# Mtx12BR.net
KiCad netlist of a schematic drawn in EAGLE
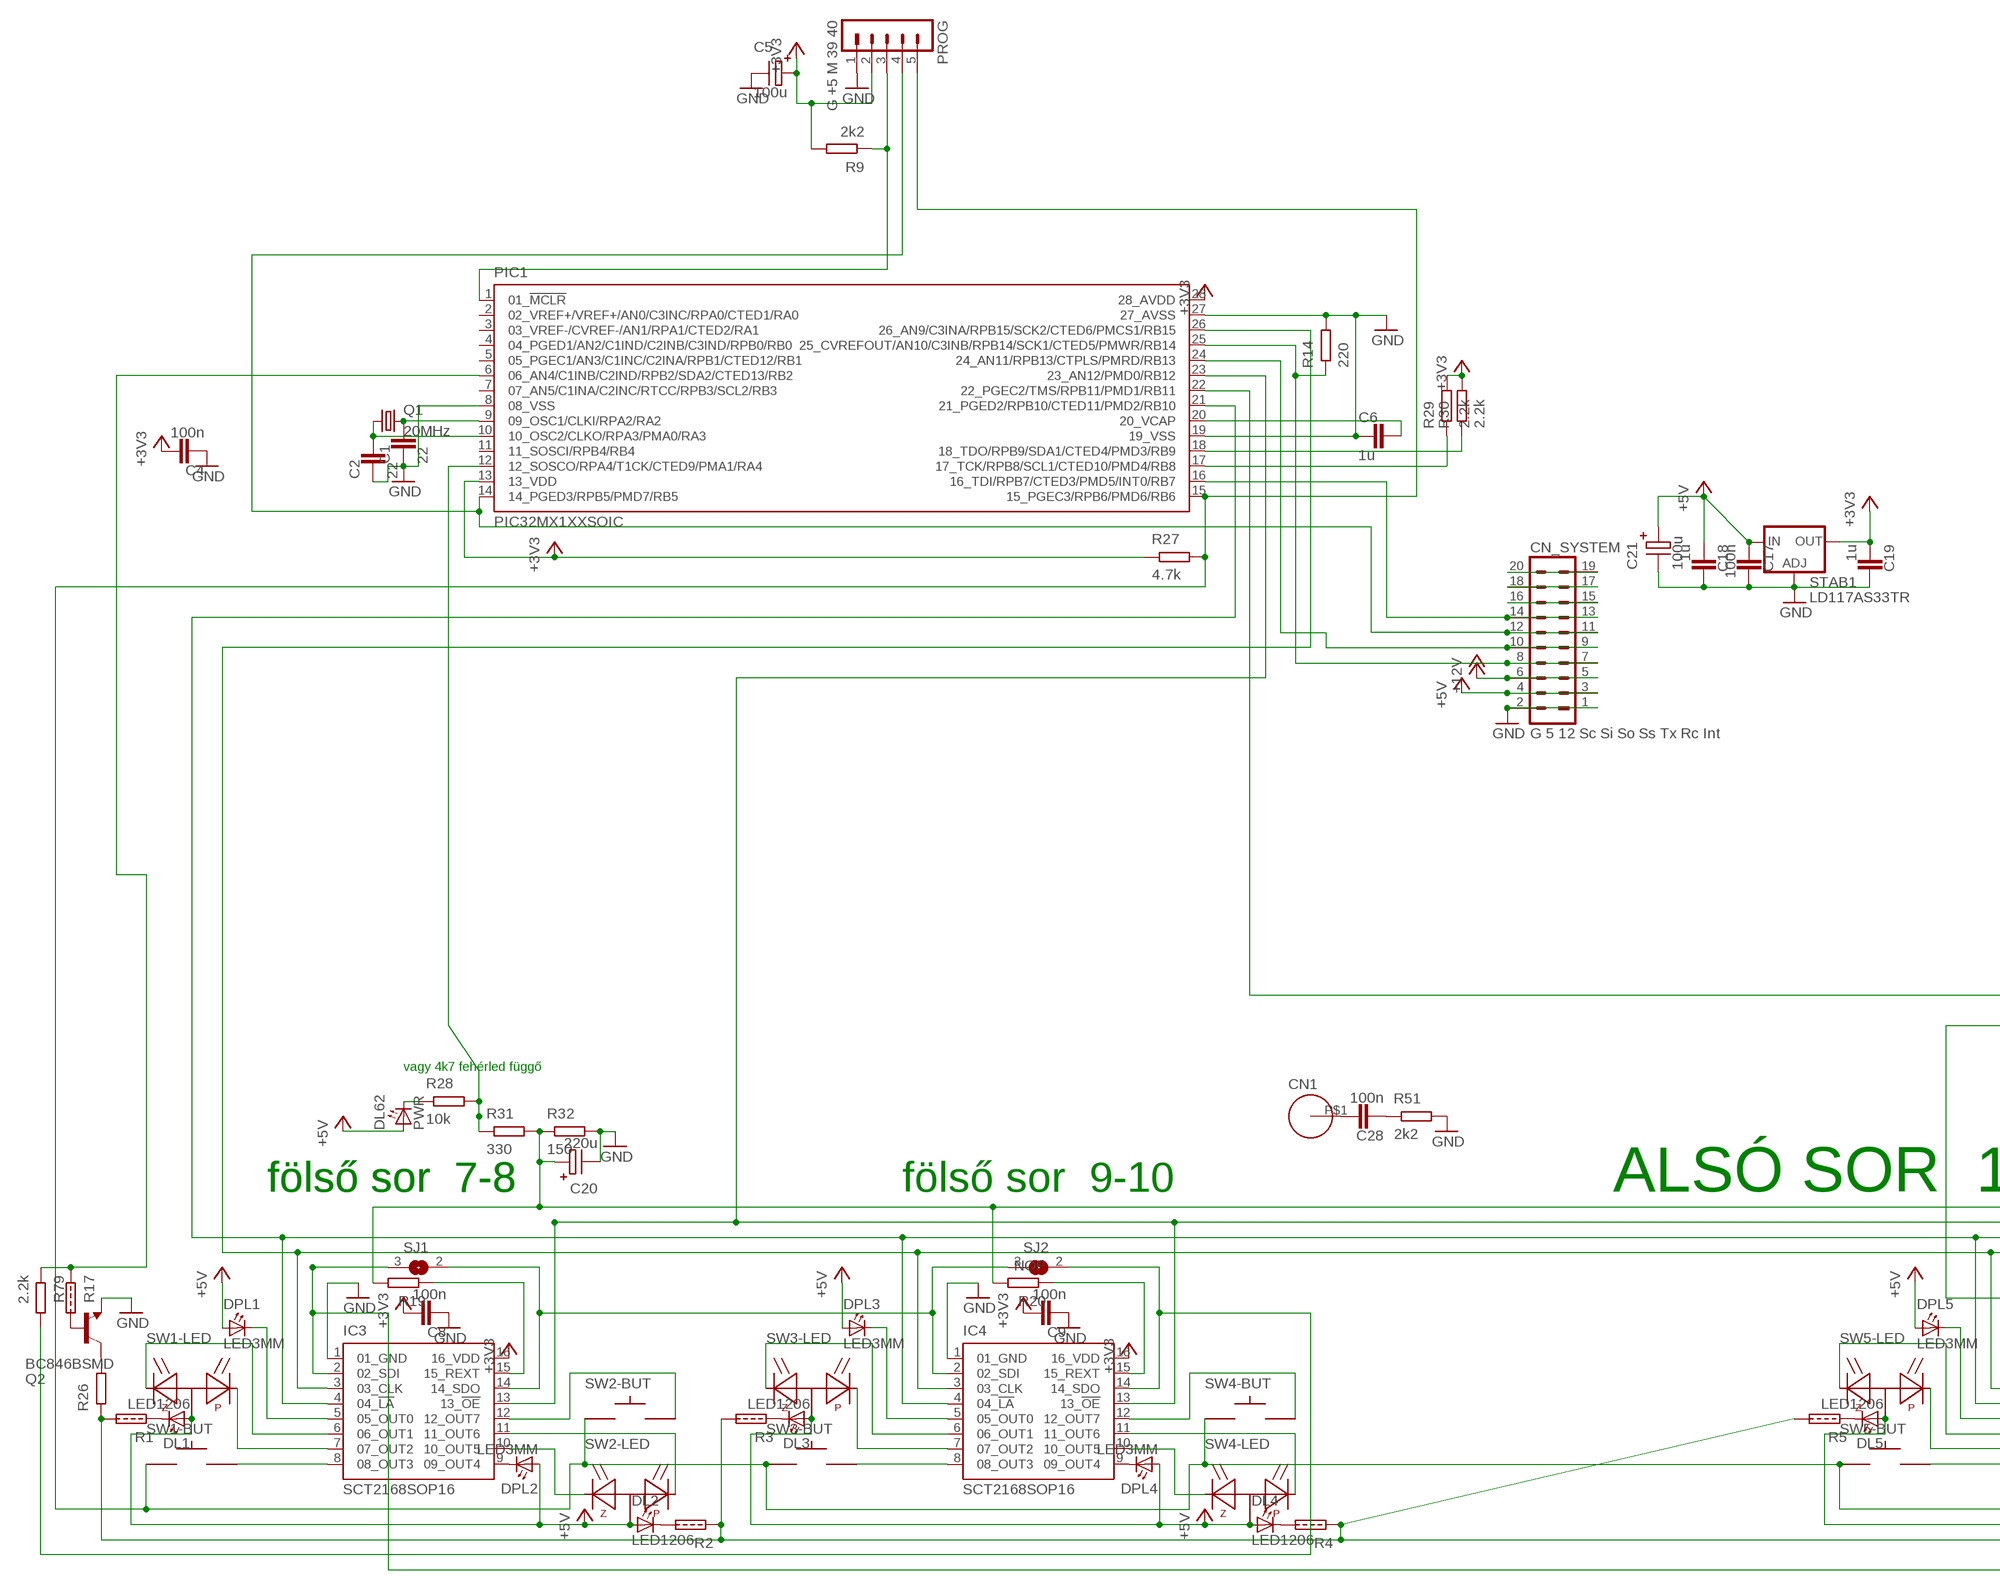
[diagram p0: schematic, sheet 1, part 1 of 2]
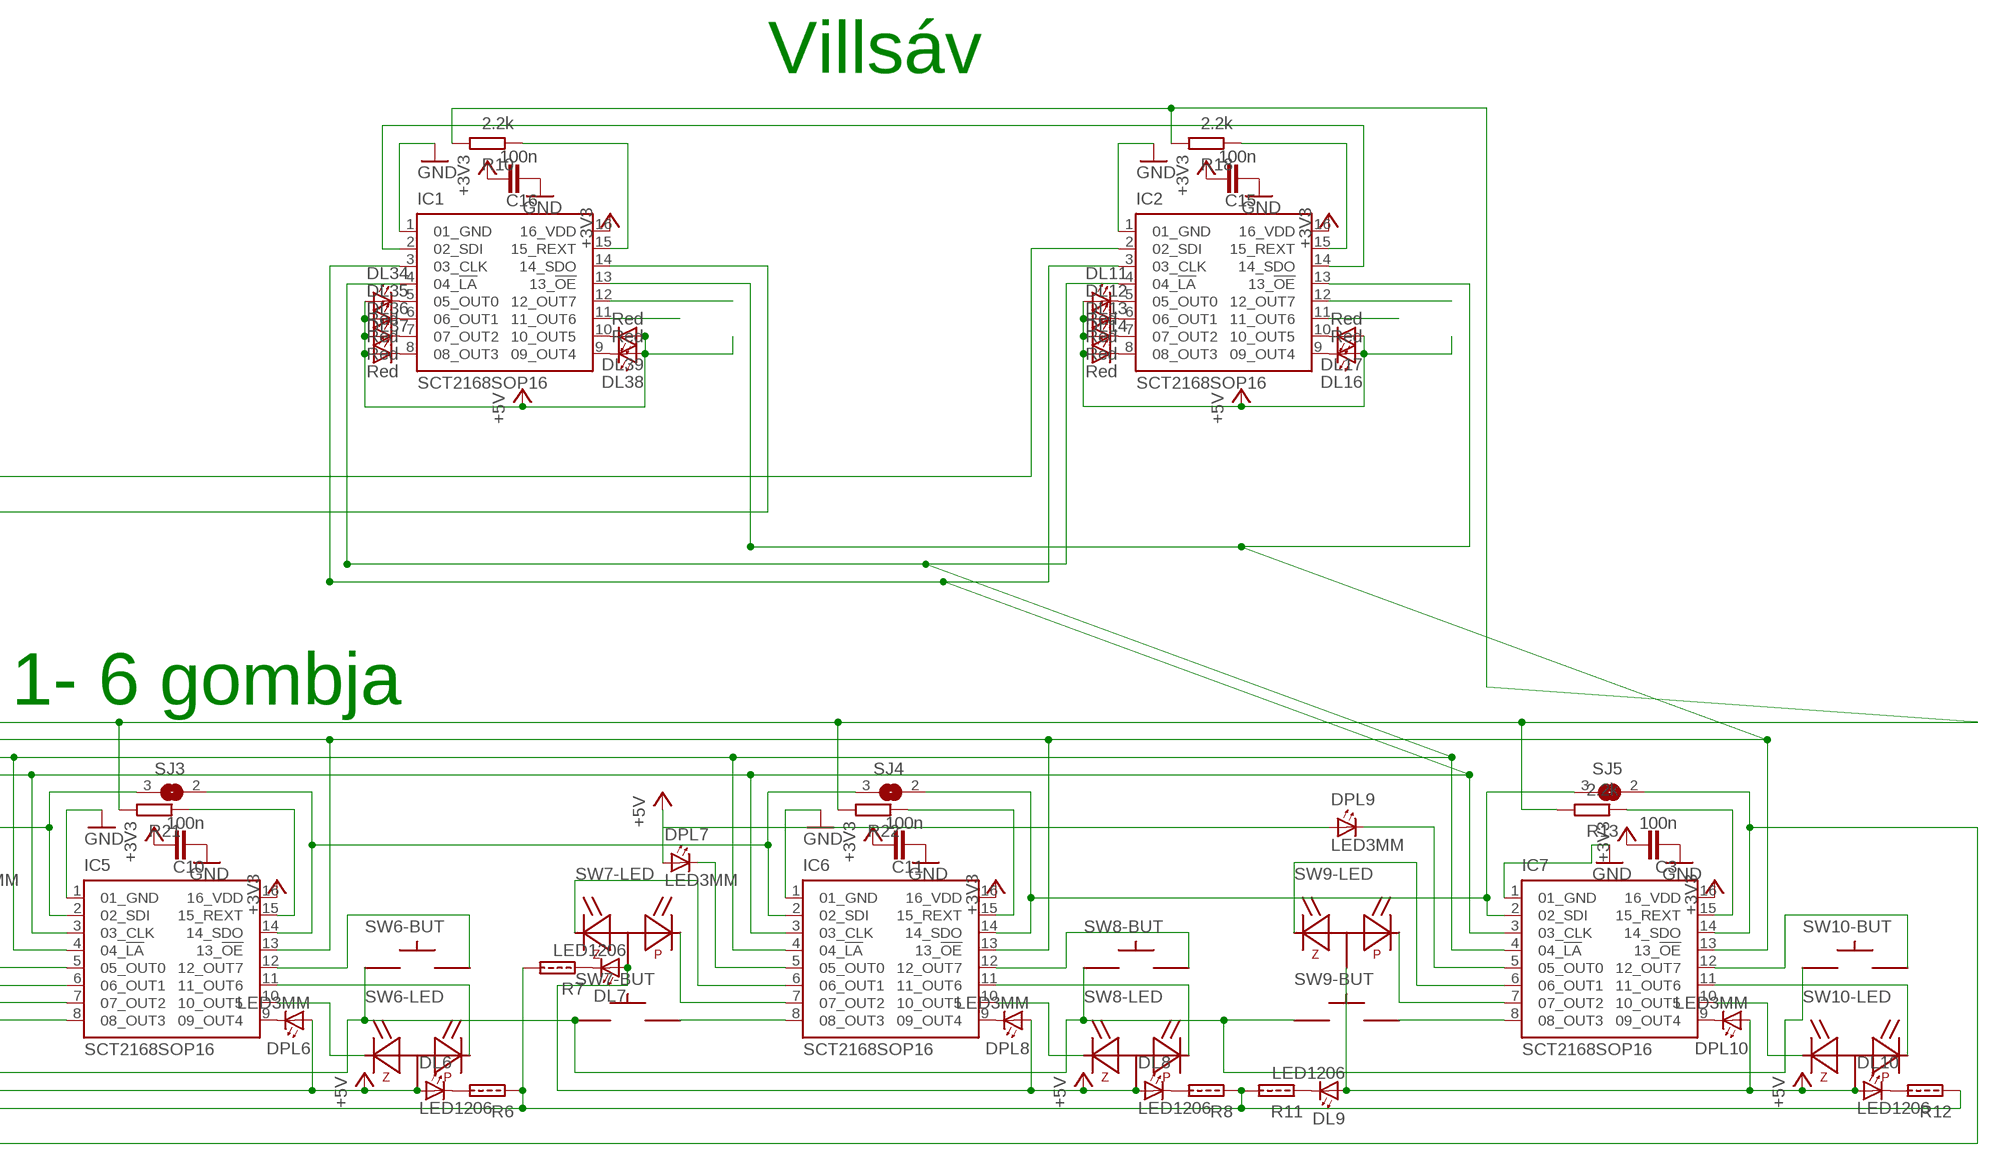
[diagram p1: schematic, sheet 1, part 2 of 2]

(export (version "E")
  (design (tool "Eeschema 10.0.6"))
  (components
    (comp (ref "C1")
      (value "22")
      (footprint "eagle-import:R0805")
      (libsource (lib "eagle-import") (part "C0805"))
    )
    (comp (ref "C2")
      (value "22")
      (footprint "eagle-import:R0805")
      (libsource (lib "eagle-import") (part "C0805"))
    )
    (comp (ref "C3")
      (value "100n")
      (footprint "eagle-import:R0805")
      (libsource (lib "eagle-import") (part "C0805"))
    )
    (comp (ref "C4")
      (value "100n")
      (footprint "eagle-import:R0805")
      (libsource (lib "eagle-import") (part "C0805"))
    )
    (comp (ref "C5")
      (value "100u")
      (footprint "eagle-import:C_EL1RASZT07")
      (libsource (lib "eagle-import") (part "C_EL1R07"))
    )
    (comp (ref "C6")
      (value "1u")
      (footprint "eagle-import:R0805")
      (libsource (lib "eagle-import") (part "C0805"))
    )
    (comp (ref "C8")
      (value "100n")
      (footprint "eagle-import:R0805")
      (libsource (lib "eagle-import") (part "C0805"))
    )
    (comp (ref "C9")
      (value "100n")
      (footprint "eagle-import:R0805")
      (libsource (lib "eagle-import") (part "C0805"))
    )
    (comp (ref "C10")
      (value "100n")
      (footprint "eagle-import:R0805")
      (libsource (lib "eagle-import") (part "C0805"))
    )
    (comp (ref "C11")
      (value "100n")
      (footprint "eagle-import:R0805")
      (libsource (lib "eagle-import") (part "C0805"))
    )
    (comp (ref "C15")
      (value "100n")
      (footprint "eagle-import:R0805")
      (libsource (lib "eagle-import") (part "C0805"))
    )
    (comp (ref "C16")
      (value "100n")
      (footprint "eagle-import:R0805")
      (libsource (lib "eagle-import") (part "C0805"))
    )
    (comp (ref "C17")
      (value "100n")
      (footprint "eagle-import:R0805")
      (libsource (lib "eagle-import") (part "C0805"))
    )
    (comp (ref "C18")
      (value "1u")
      (footprint "eagle-import:R0805")
      (libsource (lib "eagle-import") (part "C0805"))
    )
    (comp (ref "C19")
      (value "1u")
      (footprint "eagle-import:R0805")
      (libsource (lib "eagle-import") (part "C0805"))
    )
    (comp (ref "C20")
      (value "220u")
      (footprint "eagle-import:C_EL1RASZT07")
      (libsource (lib "eagle-import") (part "C_EL1R07"))
    )
    (comp (ref "C21")
      (value "100u")
      (footprint "eagle-import:C_EL1RASZT07")
      (libsource (lib "eagle-import") (part "C_EL1R07"))
    )
    (comp (ref "C28")
      (value "100n")
      (footprint "eagle-import:R0805")
      (libsource (lib "eagle-import") (part "C0805"))
    )
    (comp (ref "CN1")
      (value "TESTCSAVAR3.5")
      (footprint "eagle-import:TESTCSAVAR_3.5")
      (libsource (lib "eagle-import") (part "TESTCSAVAR3.5"))
    )
    (comp (ref "CN_SYSTEM")
      (value "G 5 12 Sc Si So Ss Tx Rc Int")
      (footprint "eagle-import:PIN10_2")
      (libsource (lib "eagle-import") (part "PIN10_2"))
    )
    (comp (ref "DL1")
      (value "LED1206")
      (footprint "eagle-import:R1206")
      (libsource (lib "eagle-import") (part "LED1206"))
    )
    (comp (ref "DL2")
      (value "LED1206")
      (footprint "eagle-import:R1206")
      (libsource (lib "eagle-import") (part "LED1206"))
    )
    (comp (ref "DL3")
      (value "LED1206")
      (footprint "eagle-import:R1206")
      (libsource (lib "eagle-import") (part "LED1206"))
    )
    (comp (ref "DL4")
      (value "LED1206")
      (footprint "eagle-import:R1206")
      (libsource (lib "eagle-import") (part "LED1206"))
    )
    (comp (ref "DL5")
      (value "LED1206")
      (footprint "eagle-import:R1206")
      (libsource (lib "eagle-import") (part "LED1206"))
    )
    (comp (ref "DL6")
      (value "LED1206")
      (footprint "eagle-import:R1206")
      (libsource (lib "eagle-import") (part "LED1206"))
    )
    (comp (ref "DL7")
      (value "LED1206")
      (footprint "eagle-import:R1206")
      (libsource (lib "eagle-import") (part "LED1206"))
    )
    (comp (ref "DL8")
      (value "LED1206")
      (footprint "eagle-import:R1206")
      (libsource (lib "eagle-import") (part "LED1206"))
    )
    (comp (ref "DL9")
      (value "LED1206")
      (footprint "eagle-import:R1206")
      (libsource (lib "eagle-import") (part "LED1206"))
    )
    (comp (ref "DL10")
      (value "LED1206")
      (footprint "eagle-import:R1206")
      (libsource (lib "eagle-import") (part "LED1206"))
    )
    (comp (ref "DL11")
      (value "Red")
      (footprint "eagle-import:LED5MM")
      (libsource (lib "eagle-import") (part "LED5MM"))
    )
    (comp (ref "DL12")
      (value "Red")
      (footprint "eagle-import:LED5MM")
      (libsource (lib "eagle-import") (part "LED5MM"))
    )
    (comp (ref "DL13")
      (value "Red")
      (footprint "eagle-import:LED5MM")
      (libsource (lib "eagle-import") (part "LED5MM"))
    )
    (comp (ref "DL14")
      (value "Red")
      (footprint "eagle-import:LED5MM")
      (libsource (lib "eagle-import") (part "LED5MM"))
    )
    (comp (ref "DL16")
      (value "Red")
      (footprint "eagle-import:LED5MM")
      (libsource (lib "eagle-import") (part "LED5MM"))
    )
    (comp (ref "DL17")
      (value "Red")
      (footprint "eagle-import:LED5MM")
      (libsource (lib "eagle-import") (part "LED5MM"))
    )
    (comp (ref "DL34")
      (value "Red")
      (footprint "eagle-import:LED5MM")
      (libsource (lib "eagle-import") (part "LED5MM"))
    )
    (comp (ref "DL35")
      (value "Red")
      (footprint "eagle-import:LED5MM")
      (libsource (lib "eagle-import") (part "LED5MM"))
    )
    (comp (ref "DL36")
      (value "Red")
      (footprint "eagle-import:LED5MM")
      (libsource (lib "eagle-import") (part "LED5MM"))
    )
    (comp (ref "DL37")
      (value "Red")
      (footprint "eagle-import:LED5MM")
      (libsource (lib "eagle-import") (part "LED5MM"))
    )
    (comp (ref "DL38")
      (value "Red")
      (footprint "eagle-import:LED5MM")
      (libsource (lib "eagle-import") (part "LED5MM"))
    )
    (comp (ref "DL39")
      (value "Red")
      (footprint "eagle-import:LED5MM")
      (libsource (lib "eagle-import") (part "LED5MM"))
    )
    (comp (ref "DL62")
      (value "PWR")
      (footprint "eagle-import:LED5MM")
      (libsource (lib "eagle-import") (part "LED5MM"))
    )
    (comp (ref "DPL1")
      (value "LED3MM")
      (footprint "eagle-import:LED3MM")
      (libsource (lib "eagle-import") (part "LED3MM"))
    )
    (comp (ref "DPL2")
      (value "LED3MM")
      (footprint "eagle-import:LED3MM")
      (libsource (lib "eagle-import") (part "LED3MM"))
    )
    (comp (ref "DPL3")
      (value "LED3MM")
      (footprint "eagle-import:LED3MM")
      (libsource (lib "eagle-import") (part "LED3MM"))
    )
    (comp (ref "DPL4")
      (value "LED3MM")
      (footprint "eagle-import:LED3MM")
      (libsource (lib "eagle-import") (part "LED3MM"))
    )
    (comp (ref "DPL5")
      (value "LED3MM")
      (footprint "eagle-import:LED3MM")
      (libsource (lib "eagle-import") (part "LED3MM"))
    )
    (comp (ref "DPL6")
      (value "LED3MM")
      (footprint "eagle-import:LED3MM")
      (libsource (lib "eagle-import") (part "LED3MM"))
    )
    (comp (ref "DPL7")
      (value "LED3MM")
      (footprint "eagle-import:LED3MM")
      (libsource (lib "eagle-import") (part "LED3MM"))
    )
    (comp (ref "DPL8")
      (value "LED3MM")
      (footprint "eagle-import:LED3MM")
      (libsource (lib "eagle-import") (part "LED3MM"))
    )
    (comp (ref "DPL9")
      (value "LED3MM")
      (footprint "eagle-import:LED3MM")
      (libsource (lib "eagle-import") (part "LED3MM"))
    )
    (comp (ref "DPL10")
      (value "LED3MM")
      (footprint "eagle-import:LED3MM")
      (libsource (lib "eagle-import") (part "LED3MM"))
    )
    (comp (ref "IC1")
      (value "SCT2168SOP16")
      (footprint "eagle-import:SO16")
      (libsource (lib "eagle-import") (part "SCT2168SOP16"))
    )
    (comp (ref "IC2")
      (value "SCT2168SOP16")
      (footprint "eagle-import:SO16")
      (libsource (lib "eagle-import") (part "SCT2168SOP16"))
    )
    (comp (ref "IC3")
      (value "SCT2168SOP16")
      (footprint "eagle-import:SO16")
      (libsource (lib "eagle-import") (part "SCT2168SOP16"))
    )
    (comp (ref "IC4")
      (value "SCT2168SOP16")
      (footprint "eagle-import:SO16")
      (libsource (lib "eagle-import") (part "SCT2168SOP16"))
    )
    (comp (ref "IC5")
      (value "SCT2168SOP16")
      (footprint "eagle-import:SO16")
      (libsource (lib "eagle-import") (part "SCT2168SOP16"))
    )
    (comp (ref "IC6")
      (value "SCT2168SOP16")
      (footprint "eagle-import:SO16")
      (libsource (lib "eagle-import") (part "SCT2168SOP16"))
    )
    (comp (ref "IC7")
      (value "SCT2168SOP16")
      (footprint "eagle-import:SO16")
      (libsource (lib "eagle-import") (part "SCT2168SOP16"))
    )
    (comp (ref "PIC1")
      (value "PIC32MX1XXSOIC")
      (footprint "eagle-import:SOIC127P1032X265-28N")
      (libsource (lib "eagle-import") (part "PIC32MX1XXSOIC"))
    )
    (comp (ref "PROG")
      (value "G +5 M 39 40")
      (footprint "eagle-import:PIN05_1")
      (libsource (lib "eagle-import") (part "PIN05_1"))
    )
    (comp (ref "Q1")
      (value "20MHz")
      (footprint "eagle-import:XTAL_NAGYSMD")
      (libsource (lib "eagle-import") (part "XTAL_2NAGYSMD"))
    )
    (comp (ref "Q2")
      (value "BC846BSMD")
      (footprint "eagle-import:SOT23")
      (libsource (lib "eagle-import") (part "BC846SMDB"))
    )
    (comp (ref "R1")
      (value "RNULL_EU0805")
      (footprint "eagle-import:R0805_C")
      (libsource (lib "eagle-import") (part "RNULL_EU0805"))
    )
    (comp (ref "R2")
      (value "RNULL_EU0805")
      (footprint "eagle-import:R0805_C")
      (libsource (lib "eagle-import") (part "RNULL_EU0805"))
    )
    (comp (ref "R3")
      (value "RNULL_EU0805")
      (footprint "eagle-import:R0805_C")
      (libsource (lib "eagle-import") (part "RNULL_EU0805"))
    )
    (comp (ref "R4")
      (value "RNULL_EU0805")
      (footprint "eagle-import:R0805_C")
      (libsource (lib "eagle-import") (part "RNULL_EU0805"))
    )
    (comp (ref "R5")
      (value "RNULL_EU0805")
      (footprint "eagle-import:R0805_C")
      (libsource (lib "eagle-import") (part "RNULL_EU0805"))
    )
    (comp (ref "R6")
      (value "RNULL_EU0805")
      (footprint "eagle-import:R0805_C")
      (libsource (lib "eagle-import") (part "RNULL_EU0805"))
    )
    (comp (ref "R7")
      (value "RNULL_EU0805")
      (footprint "eagle-import:R0805_C")
      (libsource (lib "eagle-import") (part "RNULL_EU0805"))
    )
    (comp (ref "R8")
      (value "RNULL_EU0805")
      (footprint "eagle-import:R0805_C")
      (libsource (lib "eagle-import") (part "RNULL_EU0805"))
    )
    (comp (ref "R9")
      (value "2k2")
      (footprint "eagle-import:R0805")
      (libsource (lib "eagle-import") (part "R_EU0805"))
    )
    (comp (ref "R10")
      (value "2.2k")
      (footprint "eagle-import:R0805")
      (libsource (lib "eagle-import") (part "R_EU0805"))
    )
    (comp (ref "R11")
      (value "RNULL_EU0805")
      (footprint "eagle-import:R0805_C")
      (libsource (lib "eagle-import") (part "RNULL_EU0805"))
    )
    (comp (ref "R12")
      (value "RNULL_EU0805")
      (footprint "eagle-import:R0805_C")
      (libsource (lib "eagle-import") (part "RNULL_EU0805"))
    )
    (comp (ref "R13")
      (value "2.2k")
      (footprint "eagle-import:R0805")
      (libsource (lib "eagle-import") (part "R_EU0805"))
    )
    (comp (ref "R14")
      (value "220")
      (footprint "eagle-import:R0805")
      (libsource (lib "eagle-import") (part "R_EU0805"))
    )
    (comp (ref "R17")
      (value "RNULL_EU0805")
      (footprint "eagle-import:R0805_C")
      (libsource (lib "eagle-import") (part "RNULL_EU0805"))
    )
    (comp (ref "R18")
      (value "2.2k")
      (footprint "eagle-import:R0805")
      (libsource (lib "eagle-import") (part "R_EU0805"))
    )
    (comp (ref "R19")
      (value "R_EU0805")
      (footprint "eagle-import:R0805")
      (libsource (lib "eagle-import") (part "R_EU0805"))
    )
    (comp (ref "R20")
      (value "NOP")
      (footprint "eagle-import:R0805")
      (libsource (lib "eagle-import") (part "R_EU0805"))
    )
    (comp (ref "R21")
      (value "R_EU0805")
      (footprint "eagle-import:R0805")
      (libsource (lib "eagle-import") (part "R_EU0805"))
    )
    (comp (ref "R22")
      (value "R_EU0805")
      (footprint "eagle-import:R0805")
      (libsource (lib "eagle-import") (part "R_EU0805"))
    )
    (comp (ref "R26")
      (value "R_EU0805")
      (footprint "eagle-import:R0805")
      (libsource (lib "eagle-import") (part "R_EU0805"))
    )
    (comp (ref "R27")
      (value "4.7k")
      (footprint "eagle-import:R0805")
      (libsource (lib "eagle-import") (part "R_EU0805"))
    )
    (comp (ref "R28")
      (value "10k")
      (footprint "eagle-import:R0805")
      (libsource (lib "eagle-import") (part "R_EU0805"))
    )
    (comp (ref "R29")
      (value "2.2k")
      (footprint "eagle-import:R0805")
      (libsource (lib "eagle-import") (part "R_EU0805"))
    )
    (comp (ref "R30")
      (value "2.2k")
      (footprint "eagle-import:R0805")
      (libsource (lib "eagle-import") (part "R_EU0805"))
    )
    (comp (ref "R31")
      (value "330")
      (footprint "eagle-import:R0805")
      (libsource (lib "eagle-import") (part "R_EU0805"))
    )
    (comp (ref "R32")
      (value "150")
      (footprint "eagle-import:R0805")
      (libsource (lib "eagle-import") (part "R_EU0805"))
    )
    (comp (ref "R51")
      (value "2k2")
      (footprint "eagle-import:R0805")
      (libsource (lib "eagle-import") (part "R_EU0805"))
    )
    (comp (ref "R79")
      (value "2.2k")
      (footprint "eagle-import:R0805")
      (libsource (lib "eagle-import") (part "R_EU0805"))
    )
    (comp (ref "SJ1") (value "SJ") (footprint "eagle-import:SJ") (libsource (lib "eagle-import") (part "SJ")))
    (comp (ref "SJ2") (value "SJ") (footprint "eagle-import:SJ") (libsource (lib "eagle-import") (part "SJ")))
    (comp (ref "SJ3") (value "SJ") (footprint "eagle-import:SJ") (libsource (lib "eagle-import") (part "SJ")))
    (comp (ref "SJ4") (value "SJ") (footprint "eagle-import:SJ") (libsource (lib "eagle-import") (part "SJ")))
    (comp (ref "SJ5") (value "SJ") (footprint "eagle-import:SJ") (libsource (lib "eagle-import") (part "SJ")))
    (comp (ref "STAB1")
      (value "LD117AS33TR")
      (footprint "eagle-import:SOT223")
      (libsource (lib "eagle-import") (part "LD117A?S33TR"))
    )
    (comp (ref "SW1")
      (value "SPG2")
      (footprint "eagle-import:SPG2_3LED")
      (libsource (lib "eagle-import") (part "SPG2"))
    )
    (comp (ref "SW2")
      (value "SPG2")
      (footprint "eagle-import:SPG2_3LED")
      (libsource (lib "eagle-import") (part "SPG2"))
    )
    (comp (ref "SW3")
      (value "SPG2")
      (footprint "eagle-import:SPG2_3LED")
      (libsource (lib "eagle-import") (part "SPG2"))
    )
    (comp (ref "SW4")
      (value "SPG2")
      (footprint "eagle-import:SPG2_3LED")
      (libsource (lib "eagle-import") (part "SPG2"))
    )
    (comp (ref "SW5")
      (value "SPG2")
      (footprint "eagle-import:SPG2_3LED")
      (libsource (lib "eagle-import") (part "SPG2"))
    )
    (comp (ref "SW6")
      (value "SPG2")
      (footprint "eagle-import:SPG2_3LED")
      (libsource (lib "eagle-import") (part "SPG2"))
    )
    (comp (ref "SW7")
      (value "SPG2")
      (footprint "eagle-import:SPG2_3LED")
      (libsource (lib "eagle-import") (part "SPG2"))
    )
    (comp (ref "SW8")
      (value "SPG2")
      (footprint "eagle-import:SPG2_3LED")
      (libsource (lib "eagle-import") (part "SPG2"))
    )
    (comp (ref "SW9")
      (value "SPG2")
      (footprint "eagle-import:SPG2_3LED")
      (libsource (lib "eagle-import") (part "SPG2"))
    )
    (comp (ref "SW10")
      (value "SPG2")
      (footprint "eagle-import:SPG2_3LED")
      (libsource (lib "eagle-import") (part "SPG2"))
    )
  )
  (nets
    (net (code "1") (name "+3V3") (class "Default")
      (node (ref "C10") (pin "1") (pinfunction "1_1") (pintype "passive"))
      (node (ref "C11") (pin "1") (pinfunction "1_1") (pintype "passive"))
      (node (ref "C15") (pin "1") (pinfunction "1_1") (pintype "passive"))
      (node (ref "C16") (pin "1") (pinfunction "1_1") (pintype "passive"))
      (node (ref "C19") (pin "2") (pinfunction "2_2") (pintype "passive"))
      (node (ref "C3") (pin "1") (pinfunction "1_1") (pintype "passive"))
      (node (ref "C4") (pin "1") (pinfunction "1_1") (pintype "passive"))
      (node (ref "C5") (pin "P+") (pinfunction "P+_P+") (pintype "passive"))
      (node (ref "C8") (pin "1") (pinfunction "1_1") (pintype "passive"))
      (node (ref "C9") (pin "1") (pinfunction "1_1") (pintype "passive"))
      (node (ref "IC1") (pin "16") (pinfunction "16_VDD_16") (pintype "power_in"))
      (node (ref "IC2") (pin "16") (pinfunction "16_VDD_16") (pintype "power_in"))
      (node (ref "IC3") (pin "16") (pinfunction "16_VDD_16") (pintype "power_in"))
      (node (ref "IC4") (pin "16") (pinfunction "16_VDD_16") (pintype "power_in"))
      (node (ref "IC5") (pin "16") (pinfunction "16_VDD_16") (pintype "power_in"))
      (node (ref "IC6") (pin "16") (pinfunction "16_VDD_16") (pintype "power_in"))
      (node (ref "IC7") (pin "16") (pinfunction "16_VDD_16") (pintype "power_in"))
      (node (ref "PIC1") (pin "13") (pinfunction "13_VDD_13") (pintype "bidirectional"))
      (node (ref "PIC1") (pin "28") (pinfunction "28_AVDD_28") (pintype "bidirectional"))
      (node (ref "PROG") (pin "2") (pinfunction "2_2") (pintype "passive"))
      (node (ref "R27") (pin "1") (pinfunction "A_1") (pintype "passive"))
      (node (ref "R29") (pin "2") (pinfunction "E_2") (pintype "passive"))
      (node (ref "R30") (pin "2") (pinfunction "E_2") (pintype "passive"))
      (node (ref "R9") (pin "2") (pinfunction "E_2") (pintype "passive"))
      (node (ref "STAB1") (pin "4") (pinfunction "OUT_4") (pintype "passive"))
    )
    (net (code "2") (name "+5V") (class "Default")
      (node (ref "C17") (pin "2") (pinfunction "2_2") (pintype "passive"))
      (node (ref "C18") (pin "2") (pinfunction "2_2") (pintype "passive"))
      (node (ref "C21") (pin "P+") (pinfunction "P+_P+") (pintype "passive"))
      (node (ref "CN_SYSTEM") (pin "3") (pinfunction "3_3") (pintype "passive"))
      (node (ref "CN_SYSTEM") (pin "4") (pinfunction "4_4") (pintype "passive"))
      (node (ref "DL1") (pin "1") (pinfunction "A_1") (pintype "passive"))
      (node (ref "DL10") (pin "1") (pinfunction "A_1") (pintype "passive"))
      (node (ref "DL11") (pin "A") (pinfunction "A_A") (pintype "passive"))
      (node (ref "DL12") (pin "A") (pinfunction "A_A") (pintype "passive"))
      (node (ref "DL13") (pin "A") (pinfunction "A_A") (pintype "passive"))
      (node (ref "DL14") (pin "A") (pinfunction "A_A") (pintype "passive"))
      (node (ref "DL16") (pin "A") (pinfunction "A_A") (pintype "passive"))
      (node (ref "DL17") (pin "A") (pinfunction "A_A") (pintype "passive"))
      (node (ref "DL2") (pin "1") (pinfunction "A_1") (pintype "passive"))
      (node (ref "DL3") (pin "1") (pinfunction "A_1") (pintype "passive"))
      (node (ref "DL34") (pin "A") (pinfunction "A_A") (pintype "passive"))
      (node (ref "DL35") (pin "A") (pinfunction "A_A") (pintype "passive"))
      (node (ref "DL36") (pin "A") (pinfunction "A_A") (pintype "passive"))
      (node (ref "DL37") (pin "A") (pinfunction "A_A") (pintype "passive"))
      (node (ref "DL38") (pin "A") (pinfunction "A_A") (pintype "passive"))
      (node (ref "DL39") (pin "A") (pinfunction "A_A") (pintype "passive"))
      (node (ref "DL4") (pin "1") (pinfunction "A_1") (pintype "passive"))
      (node (ref "DL5") (pin "1") (pinfunction "A_1") (pintype "passive"))
      (node (ref "DL6") (pin "1") (pinfunction "A_1") (pintype "passive"))
      (node (ref "DL62") (pin "A") (pinfunction "A_A") (pintype "passive"))
      (node (ref "DL7") (pin "1") (pinfunction "A_1") (pintype "passive"))
      (node (ref "DL8") (pin "1") (pinfunction "A_1") (pintype "passive"))
      (node (ref "DL9") (pin "1") (pinfunction "A_1") (pintype "passive"))
      (node (ref "DPL1") (pin "A") (pinfunction "A_A") (pintype "passive"))
      (node (ref "DPL10") (pin "A") (pinfunction "A_A") (pintype "passive"))
      (node (ref "DPL2") (pin "A") (pinfunction "A_A") (pintype "passive"))
      (node (ref "DPL3") (pin "A") (pinfunction "A_A") (pintype "passive"))
      (node (ref "DPL4") (pin "A") (pinfunction "A_A") (pintype "passive"))
      (node (ref "DPL5") (pin "A") (pinfunction "A_A") (pintype "passive"))
      (node (ref "DPL6") (pin "A") (pinfunction "A_A") (pintype "passive"))
      (node (ref "DPL7") (pin "A") (pinfunction "A_A") (pintype "passive"))
      (node (ref "DPL8") (pin "A") (pinfunction "A_A") (pintype "passive"))
      (node (ref "DPL9") (pin "A") (pinfunction "A_A") (pintype "passive"))
      (node (ref "STAB1") (pin "3") (pinfunction "IN_3") (pintype "input"))
      (node (ref "SW1") (pin "LED+") (pinfunction "+_LED+") (pintype "bidirectional"))
      (node (ref "SW10") (pin "LED+") (pinfunction "+_LED+") (pintype "bidirectional"))
      (node (ref "SW2") (pin "LED+") (pinfunction "+_LED+") (pintype "bidirectional"))
      (node (ref "SW3") (pin "LED+") (pinfunction "+_LED+") (pintype "bidirectional"))
      (node (ref "SW4") (pin "LED+") (pinfunction "+_LED+") (pintype "bidirectional"))
      (node (ref "SW5") (pin "LED+") (pinfunction "+_LED+") (pintype "bidirectional"))
      (node (ref "SW6") (pin "LED+") (pinfunction "+_LED+") (pintype "bidirectional"))
      (node (ref "SW7") (pin "LED+") (pinfunction "+_LED+") (pintype "bidirectional"))
      (node (ref "SW8") (pin "LED+") (pinfunction "+_LED+") (pintype "bidirectional"))
      (node (ref "SW9") (pin "LED+") (pinfunction "+_LED+") (pintype "bidirectional"))
    )
    (net (code "3") (name "+12V") (class "Default")
      (node (ref "CN_SYSTEM") (pin "5") (pinfunction "5_5") (pintype "passive"))
      (node (ref "CN_SYSTEM") (pin "6") (pinfunction "6_6") (pintype "passive"))
    )
    (net (code "4") (name "GND") (class "Default")
      (node (ref "C1") (pin "2") (pinfunction "2_2") (pintype "passive"))
      (node (ref "C10") (pin "2") (pinfunction "2_2") (pintype "passive"))
      (node (ref "C11") (pin "2") (pinfunction "2_2") (pintype "passive"))
      (node (ref "C15") (pin "2") (pinfunction "2_2") (pintype "passive"))
      (node (ref "C16") (pin "2") (pinfunction "2_2") (pintype "passive"))
      (node (ref "C17") (pin "1") (pinfunction "1_1") (pintype "passive"))
      (node (ref "C18") (pin "1") (pinfunction "1_1") (pintype "passive"))
      (node (ref "C19") (pin "1") (pinfunction "1_1") (pintype "passive"))
      (node (ref "C2") (pin "2") (pinfunction "2_2") (pintype "passive"))
      (node (ref "C20") (pin "P-") (pinfunction "P-_P-") (pintype "passive"))
      (node (ref "C21") (pin "P-") (pinfunction "P-_P-") (pintype "passive"))
      (node (ref "C3") (pin "2") (pinfunction "2_2") (pintype "passive"))
      (node (ref "C4") (pin "2") (pinfunction "2_2") (pintype "passive"))
      (node (ref "C5") (pin "P-") (pinfunction "P-_P-") (pintype "passive"))
      (node (ref "C6") (pin "2") (pinfunction "2_2") (pintype "passive"))
      (node (ref "C8") (pin "2") (pinfunction "2_2") (pintype "passive"))
      (node (ref "C9") (pin "2") (pinfunction "2_2") (pintype "passive"))
      (node (ref "CN_SYSTEM") (pin "1") (pinfunction "1_1") (pintype "passive"))
      (node (ref "CN_SYSTEM") (pin "2") (pinfunction "2_2") (pintype "passive"))
      (node (ref "IC1") (pin "1") (pinfunction "01_GND_1") (pintype "power_in"))
      (node (ref "IC2") (pin "1") (pinfunction "01_GND_1") (pintype "power_in"))
      (node (ref "IC3") (pin "1") (pinfunction "01_GND_1") (pintype "power_in"))
      (node (ref "IC4") (pin "1") (pinfunction "01_GND_1") (pintype "power_in"))
      (node (ref "IC5") (pin "1") (pinfunction "01_GND_1") (pintype "power_in"))
      (node (ref "IC6") (pin "1") (pinfunction "01_GND_1") (pintype "power_in"))
      (node (ref "IC7") (pin "1") (pinfunction "01_GND_1") (pintype "power_in"))
      (node (ref "PIC1") (pin "19") (pinfunction "19_VSS_19") (pintype "power_in"))
      (node (ref "PIC1") (pin "27") (pinfunction "27_AVSS_27") (pintype "bidirectional"))
      (node (ref "PIC1") (pin "8") (pinfunction "08_VSS_8") (pintype "power_in"))
      (node (ref "PROG") (pin "1") (pinfunction "1_1") (pintype "passive"))
      (node (ref "Q2") (pin "2") (pinfunction "E_2") (pintype "passive"))
      (node (ref "R14") (pin "2") (pinfunction "E_2") (pintype "passive"))
      (node (ref "R32") (pin "2") (pinfunction "E_2") (pintype "passive"))
      (node (ref "R51") (pin "2") (pinfunction "E_2") (pintype "passive"))
      (node (ref "STAB1") (pin "1") (pinfunction "ADJ_1") (pintype "input"))
    )
    (net (code "5") (name "Net-(CN1-1)") (class "Default")
      (node (ref "C28") (pin "1") (pinfunction "1_1") (pintype "passive"))
      (node (ref "CN1") (pin "P$1") (pinfunction "1_P$1") (pintype "passive"))
    )
    (net (code "6") (name "Net-(CN_SYSTEM-Pad15)") (class "Default")
      (node (ref "CN_SYSTEM") (pin "15") (pinfunction "15_15") (pintype "passive"))
      (node (ref "CN_SYSTEM") (pin "16") (pinfunction "16_16") (pintype "passive"))
    )
    (net (code "7") (name "Net-(CN_SYSTEM-Pad17)") (class "Default")
      (node (ref "CN_SYSTEM") (pin "17") (pinfunction "17_17") (pintype "passive"))
      (node (ref "CN_SYSTEM") (pin "18") (pinfunction "18_18") (pintype "passive"))
    )
    (net (code "8") (name "Net-(CN_SYSTEM-Pad19)") (class "Default")
      (node (ref "CN_SYSTEM") (pin "19") (pinfunction "19_19") (pintype "passive"))
      (node (ref "CN_SYSTEM") (pin "20") (pinfunction "20_20") (pintype "passive"))
    )
    (net (code "9") (name "Net-(DL1-C)") (class "Default")
      (node (ref "DL1") (pin "2") (pinfunction "C_2") (pintype "passive"))
      (node (ref "R1") (pin "1") (pinfunction "A_1") (pintype "passive"))
    )
    (net (code "10") (name "Net-(DL2-C)") (class "Default")
      (node (ref "DL2") (pin "2") (pinfunction "C_2") (pintype "passive"))
      (node (ref "R2") (pin "2") (pinfunction "E_2") (pintype "passive"))
    )
    (net (code "11") (name "Net-(DL3-C)") (class "Default")
      (node (ref "DL3") (pin "2") (pinfunction "C_2") (pintype "passive"))
      (node (ref "R3") (pin "1") (pinfunction "A_1") (pintype "passive"))
    )
    (net (code "12") (name "Net-(DL4-C)") (class "Default")
      (node (ref "DL4") (pin "2") (pinfunction "C_2") (pintype "passive"))
      (node (ref "R4") (pin "2") (pinfunction "E_2") (pintype "passive"))
    )
    (net (code "13") (name "Net-(DL5-C)") (class "Default")
      (node (ref "DL5") (pin "2") (pinfunction "C_2") (pintype "passive"))
      (node (ref "R5") (pin "1") (pinfunction "A_1") (pintype "passive"))
    )
    (net (code "14") (name "Net-(DL6-C)") (class "Default")
      (node (ref "DL6") (pin "2") (pinfunction "C_2") (pintype "passive"))
      (node (ref "R6") (pin "2") (pinfunction "E_2") (pintype "passive"))
    )
    (net (code "15") (name "Net-(DL7-C)") (class "Default")
      (node (ref "DL7") (pin "2") (pinfunction "C_2") (pintype "passive"))
      (node (ref "R7") (pin "1") (pinfunction "A_1") (pintype "passive"))
    )
    (net (code "16") (name "Net-(DL8-C)") (class "Default")
      (node (ref "DL8") (pin "2") (pinfunction "C_2") (pintype "passive"))
      (node (ref "R8") (pin "2") (pinfunction "E_2") (pintype "passive"))
    )
    (net (code "17") (name "Net-(DL9-C)") (class "Default")
      (node (ref "DL9") (pin "2") (pinfunction "C_2") (pintype "passive"))
      (node (ref "R11") (pin "1") (pinfunction "A_1") (pintype "passive"))
    )
    (net (code "18") (name "Net-(DL10-C)") (class "Default")
      (node (ref "DL10") (pin "2") (pinfunction "C_2") (pintype "passive"))
      (node (ref "R12") (pin "2") (pinfunction "E_2") (pintype "passive"))
    )
    (net (code "19") (name "Net-(DL11-C)") (class "Default")
      (node (ref "DL11") (pin "K") (pinfunction "C_K") (pintype "passive"))
      (node (ref "IC2") (pin "5") (pinfunction "05_OUT0_5") (pintype "output"))
    )
    (net (code "20") (name "Net-(DL12-C)") (class "Default")
      (node (ref "DL12") (pin "K") (pinfunction "C_K") (pintype "passive"))
      (node (ref "IC2") (pin "6") (pinfunction "06_OUT1_6") (pintype "output"))
    )
    (net (code "21") (name "Net-(DL13-C)") (class "Default")
      (node (ref "DL13") (pin "K") (pinfunction "C_K") (pintype "passive"))
      (node (ref "IC2") (pin "7") (pinfunction "07_OUT2_7") (pintype "output"))
    )
    (net (code "22") (name "Net-(DL14-C)") (class "Default")
      (node (ref "DL14") (pin "K") (pinfunction "C_K") (pintype "passive"))
      (node (ref "IC2") (pin "8") (pinfunction "08_OUT3_8") (pintype "output"))
    )
    (net (code "23") (name "Net-(DL16-C)") (class "Default")
      (node (ref "DL16") (pin "K") (pinfunction "C_K") (pintype "passive"))
      (node (ref "IC2") (pin "9") (pinfunction "09_OUT4_9") (pintype "output"))
    )
    (net (code "24") (name "Net-(DL17-C)") (class "Default")
      (node (ref "DL17") (pin "K") (pinfunction "C_K") (pintype "passive"))
      (node (ref "IC2") (pin "10") (pinfunction "10_OUT5_10") (pintype "output"))
    )
    (net (code "25") (name "Net-(DL34-C)") (class "Default")
      (node (ref "DL34") (pin "K") (pinfunction "C_K") (pintype "passive"))
      (node (ref "IC1") (pin "5") (pinfunction "05_OUT0_5") (pintype "output"))
    )
    (net (code "26") (name "Net-(DL35-C)") (class "Default")
      (node (ref "DL35") (pin "K") (pinfunction "C_K") (pintype "passive"))
      (node (ref "IC1") (pin "6") (pinfunction "06_OUT1_6") (pintype "output"))
    )
    (net (code "27") (name "Net-(DL36-C)") (class "Default")
      (node (ref "DL36") (pin "K") (pinfunction "C_K") (pintype "passive"))
      (node (ref "IC1") (pin "7") (pinfunction "07_OUT2_7") (pintype "output"))
    )
    (net (code "28") (name "Net-(DL37-C)") (class "Default")
      (node (ref "DL37") (pin "K") (pinfunction "C_K") (pintype "passive"))
      (node (ref "IC1") (pin "8") (pinfunction "08_OUT3_8") (pintype "output"))
    )
    (net (code "29") (name "Net-(DL38-C)") (class "Default")
      (node (ref "DL38") (pin "K") (pinfunction "C_K") (pintype "passive"))
      (node (ref "IC1") (pin "9") (pinfunction "09_OUT4_9") (pintype "output"))
    )
    (net (code "30") (name "Net-(DL39-C)") (class "Default")
      (node (ref "DL39") (pin "K") (pinfunction "C_K") (pintype "passive"))
      (node (ref "IC1") (pin "10") (pinfunction "10_OUT5_10") (pintype "output"))
    )
    (net (code "31") (name "Net-(DL62-C)") (class "Default")
      (node (ref "DL62") (pin "K") (pinfunction "C_K") (pintype "passive"))
      (node (ref "R28") (pin "1") (pinfunction "A_1") (pintype "passive"))
    )
    (net (code "32") (name "Net-(DPL1-C)") (class "Default")
      (node (ref "DPL1") (pin "K") (pinfunction "C_K") (pintype "passive"))
      (node (ref "IC3") (pin "5") (pinfunction "05_OUT0_5") (pintype "output"))
    )
    (net (code "33") (name "Net-(DPL2-C)") (class "Default")
      (node (ref "DPL2") (pin "K") (pinfunction "C_K") (pintype "passive"))
      (node (ref "IC3") (pin "9") (pinfunction "09_OUT4_9") (pintype "output"))
    )
    (net (code "34") (name "Net-(DPL3-C)") (class "Default")
      (node (ref "DPL3") (pin "K") (pinfunction "C_K") (pintype "passive"))
      (node (ref "IC4") (pin "5") (pinfunction "05_OUT0_5") (pintype "output"))
    )
    (net (code "35") (name "Net-(DPL4-C)") (class "Default")
      (node (ref "DPL4") (pin "K") (pinfunction "C_K") (pintype "passive"))
      (node (ref "IC4") (pin "9") (pinfunction "09_OUT4_9") (pintype "output"))
    )
    (net (code "36") (name "Net-(DPL5-C)") (class "Default")
      (node (ref "DPL5") (pin "K") (pinfunction "C_K") (pintype "passive"))
      (node (ref "IC5") (pin "5") (pinfunction "05_OUT0_5") (pintype "output"))
    )
    (net (code "37") (name "Net-(DPL6-C)") (class "Default")
      (node (ref "DPL6") (pin "K") (pinfunction "C_K") (pintype "passive"))
      (node (ref "IC5") (pin "9") (pinfunction "09_OUT4_9") (pintype "output"))
    )
    (net (code "38") (name "Net-(DPL7-C)") (class "Default")
      (node (ref "DPL7") (pin "K") (pinfunction "C_K") (pintype "passive"))
      (node (ref "IC6") (pin "5") (pinfunction "05_OUT0_5") (pintype "output"))
    )
    (net (code "39") (name "Net-(DPL8-C)") (class "Default")
      (node (ref "DPL8") (pin "K") (pinfunction "C_K") (pintype "passive"))
      (node (ref "IC6") (pin "9") (pinfunction "09_OUT4_9") (pintype "output"))
    )
    (net (code "40") (name "Net-(DPL9-C)") (class "Default")
      (node (ref "DPL9") (pin "K") (pinfunction "C_K") (pintype "passive"))
      (node (ref "IC7") (pin "5") (pinfunction "05_OUT0_5") (pintype "output"))
    )
    (net (code "41") (name "Net-(DPL10-C)") (class "Default")
      (node (ref "DPL10") (pin "K") (pinfunction "C_K") (pintype "passive"))
      (node (ref "IC7") (pin "9") (pinfunction "09_OUT4_9") (pintype "output"))
    )
    (net (code "42") (name "Net-(IC1-02_SDI)") (class "Default")
      (node (ref "IC1") (pin "2") (pinfunction "02_SDI_2") (pintype "input"))
      (node (ref "IC2") (pin "14") (pinfunction "14_SDO_14") (pintype "output"))
    )
    (net (code "43") (name "Net-(IC1-03_CLK)") (class "Default")
      (node (ref "IC1") (pin "3") (pinfunction "03_CLK_3") (pintype "input"))
      (node (ref "IC2") (pin "3") (pinfunction "03_CLK_3") (pintype "input"))
      (node (ref "IC3") (pin "3") (pinfunction "03_CLK_3") (pintype "input"))
      (node (ref "IC4") (pin "3") (pinfunction "03_CLK_3") (pintype "input"))
      (node (ref "IC5") (pin "3") (pinfunction "03_CLK_3") (pintype "input"))
      (node (ref "IC6") (pin "3") (pinfunction "03_CLK_3") (pintype "input"))
      (node (ref "IC7") (pin "3") (pinfunction "03_CLK_3") (pintype "input"))
      (node (ref "PIC1") (pin "26") (pinfunction "26_AN9/C3INA/RPB15/SCK2/CTED6/PMCS1/RB15_26") (pintype "bidirectional"))
    )
    (net (code "44") (name "Net-(IC1-04_~{LA})") (class "Default")
      (node (ref "IC1") (pin "4") (pinfunction "04_~{LA}_4") (pintype "input"))
      (node (ref "IC2") (pin "4") (pinfunction "04_~{LA}_4") (pintype "input"))
      (node (ref "IC3") (pin "4") (pinfunction "04_~{LA}_4") (pintype "input"))
      (node (ref "IC4") (pin "4") (pinfunction "04_~{LA}_4") (pintype "input"))
      (node (ref "IC5") (pin "4") (pinfunction "04_~{LA}_4") (pintype "input"))
      (node (ref "IC6") (pin "4") (pinfunction "04_~{LA}_4") (pintype "input"))
      (node (ref "IC7") (pin "4") (pinfunction "04_~{LA}_4") (pintype "input"))
      (node (ref "PIC1") (pin "21") (pinfunction "21_PGED2/RPB10/CTED11/PMD2/RB10_21") (pintype "bidirectional"))
    )
    (net (code "45") (name "Net-(IC1-13_~{OE})") (class "Default")
      (node (ref "IC1") (pin "13") (pinfunction "13_~{OE}_13") (pintype "input"))
      (node (ref "IC2") (pin "13") (pinfunction "13_~{OE}_13") (pintype "input"))
      (node (ref "IC3") (pin "13") (pinfunction "13_~{OE}_13") (pintype "input"))
      (node (ref "IC4") (pin "13") (pinfunction "13_~{OE}_13") (pintype "input"))
      (node (ref "IC5") (pin "13") (pinfunction "13_~{OE}_13") (pintype "input"))
      (node (ref "IC6") (pin "13") (pinfunction "13_~{OE}_13") (pintype "input"))
      (node (ref "IC7") (pin "13") (pinfunction "13_~{OE}_13") (pintype "input"))
      (node (ref "PIC1") (pin "23") (pinfunction "23_AN12/PMD0/RB12_23") (pintype "bidirectional"))
    )
    (net (code "46") (name "Net-(IC1-14_SDO)") (class "Default")
      (node (ref "IC1") (pin "14") (pinfunction "14_SDO_14") (pintype "output"))
      (node (ref "IC5") (pin "2") (pinfunction "02_SDI_2") (pintype "input"))
      (node (ref "SJ3") (pin "3") (pinfunction "1_3") (pintype "passive"))
    )
    (net (code "47") (name "Net-(IC1-15_REXT)") (class "Default")
      (node (ref "IC1") (pin "15") (pinfunction "15_REXT_15") (pintype "bidirectional"))
      (node (ref "R10") (pin "1") (pinfunction "A_1") (pintype "passive"))
    )
    (net (code "48") (name "Net-(IC2-02_SDI)") (class "Default")
      (node (ref "IC2") (pin "2") (pinfunction "02_SDI_2") (pintype "input"))
      (node (ref "PIC1") (pin "22") (pinfunction "22_PGEC2/TMS/RPB11/PMD1/RB11_22") (pintype "bidirectional"))
    )
    (net (code "49") (name "Net-(IC2-15_REXT)") (class "Default")
      (node (ref "IC2") (pin "15") (pinfunction "15_REXT_15") (pintype "bidirectional"))
      (node (ref "R18") (pin "1") (pinfunction "A_1") (pintype "passive"))
    )
    (net (code "50") (name "Net-(IC3-02_SDI)") (class "Default")
      (node (ref "IC3") (pin "2") (pinfunction "02_SDI_2") (pintype "input"))
      (node (ref "IC7") (pin "14") (pinfunction "14_SDO_14") (pintype "output"))
      (node (ref "SJ1") (pin "3") (pinfunction "1_3") (pintype "passive"))
      (node (ref "SJ5") (pin "2") (pinfunction "2_2") (pintype "passive"))
    )
    (net (code "51") (name "Net-(IC3-06_OUT1)") (class "Default")
      (node (ref "IC3") (pin "6") (pinfunction "06_OUT1_6") (pintype "output"))
      (node (ref "SW1") (pin "Z-") (pinfunction "Z_Z-") (pintype "bidirectional"))
    )
    (net (code "52") (name "Net-(IC3-07_OUT2)") (class "Default")
      (node (ref "IC3") (pin "7") (pinfunction "07_OUT2_7") (pintype "output"))
      (node (ref "SW1") (pin "P-") (pinfunction "P_P-") (pintype "bidirectional"))
    )
    (net (code "53") (name "Net-(IC3-08_OUT3)") (class "Default")
      (node (ref "IC3") (pin "8") (pinfunction "08_OUT3_8") (pintype "output"))
      (node (ref "SW1") (pin "G2") (pinfunction "G2_G2") (pintype "bidirectional"))
    )
    (net (code "54") (name "Net-(IC3-10_OUT5)") (class "Default")
      (node (ref "IC3") (pin "10") (pinfunction "10_OUT5_10") (pintype "output"))
      (node (ref "SW2") (pin "Z-") (pinfunction "Z_Z-") (pintype "bidirectional"))
    )
    (net (code "55") (name "Net-(IC3-11_OUT6)") (class "Default")
      (node (ref "IC3") (pin "11") (pinfunction "11_OUT6_11") (pintype "output"))
      (node (ref "SW2") (pin "P-") (pinfunction "P_P-") (pintype "bidirectional"))
    )
    (net (code "56") (name "Net-(IC3-12_OUT7)") (class "Default")
      (node (ref "IC3") (pin "12") (pinfunction "12_OUT7_12") (pintype "output"))
      (node (ref "SW2") (pin "G2") (pinfunction "G2_G2") (pintype "bidirectional"))
    )
    (net (code "57") (name "Net-(IC3-14_SDO)") (class "Default")
      (node (ref "IC3") (pin "14") (pinfunction "14_SDO_14") (pintype "output"))
      (node (ref "IC4") (pin "2") (pinfunction "02_SDI_2") (pintype "input"))
      (node (ref "SJ1") (pin "2") (pinfunction "2_2") (pintype "passive"))
      (node (ref "SJ2") (pin "3") (pinfunction "1_3") (pintype "passive"))
    )
    (net (code "58") (name "Net-(IC3-15_REXT)") (class "Default")
      (node (ref "IC3") (pin "15") (pinfunction "15_REXT_15") (pintype "bidirectional"))
      (node (ref "R19") (pin "1") (pinfunction "A_1") (pintype "passive"))
    )
    (net (code "59") (name "Net-(IC4-06_OUT1)") (class "Default")
      (node (ref "IC4") (pin "6") (pinfunction "06_OUT1_6") (pintype "output"))
      (node (ref "SW3") (pin "Z-") (pinfunction "Z_Z-") (pintype "bidirectional"))
    )
    (net (code "60") (name "Net-(IC4-07_OUT2)") (class "Default")
      (node (ref "IC4") (pin "7") (pinfunction "07_OUT2_7") (pintype "output"))
      (node (ref "SW3") (pin "P-") (pinfunction "P_P-") (pintype "bidirectional"))
    )
    (net (code "61") (name "Net-(IC4-08_OUT3)") (class "Default")
      (node (ref "IC4") (pin "8") (pinfunction "08_OUT3_8") (pintype "output"))
      (node (ref "SW3") (pin "G2") (pinfunction "G2_G2") (pintype "bidirectional"))
    )
    (net (code "62") (name "Net-(IC4-10_OUT5)") (class "Default")
      (node (ref "IC4") (pin "10") (pinfunction "10_OUT5_10") (pintype "output"))
      (node (ref "SW4") (pin "Z-") (pinfunction "Z_Z-") (pintype "bidirectional"))
    )
    (net (code "63") (name "Net-(IC4-11_OUT6)") (class "Default")
      (node (ref "IC4") (pin "11") (pinfunction "11_OUT6_11") (pintype "output"))
      (node (ref "SW4") (pin "P-") (pinfunction "P_P-") (pintype "bidirectional"))
    )
    (net (code "64") (name "Net-(IC4-12_OUT7)") (class "Default")
      (node (ref "IC4") (pin "12") (pinfunction "12_OUT7_12") (pintype "output"))
      (node (ref "SW4") (pin "G2") (pinfunction "G2_G2") (pintype "bidirectional"))
    )
    (net (code "65") (name "Net-(IC4-14_SDO)") (class "Default")
      (node (ref "IC4") (pin "14") (pinfunction "14_SDO_14") (pintype "output"))
      (node (ref "R79") (pin "2") (pinfunction "E_2") (pintype "passive"))
      (node (ref "SJ2") (pin "2") (pinfunction "2_2") (pintype "passive"))
    )
    (net (code "66") (name "Net-(IC4-15_REXT)") (class "Default")
      (node (ref "IC4") (pin "15") (pinfunction "15_REXT_15") (pintype "bidirectional"))
      (node (ref "R20") (pin "1") (pinfunction "A_1") (pintype "passive"))
    )
    (net (code "67") (name "Net-(IC5-06_OUT1)") (class "Default")
      (node (ref "IC5") (pin "6") (pinfunction "06_OUT1_6") (pintype "output"))
      (node (ref "SW5") (pin "Z-") (pinfunction "Z_Z-") (pintype "bidirectional"))
    )
    (net (code "68") (name "Net-(IC5-07_OUT2)") (class "Default")
      (node (ref "IC5") (pin "7") (pinfunction "07_OUT2_7") (pintype "output"))
      (node (ref "SW5") (pin "P-") (pinfunction "P_P-") (pintype "bidirectional"))
    )
    (net (code "69") (name "Net-(IC5-08_OUT3)") (class "Default")
      (node (ref "IC5") (pin "8") (pinfunction "08_OUT3_8") (pintype "output"))
      (node (ref "SW5") (pin "G2") (pinfunction "G2_G2") (pintype "bidirectional"))
    )
    (net (code "70") (name "Net-(IC5-10_OUT5)") (class "Default")
      (node (ref "IC5") (pin "10") (pinfunction "10_OUT5_10") (pintype "output"))
      (node (ref "SW6") (pin "Z-") (pinfunction "Z_Z-") (pintype "bidirectional"))
    )
    (net (code "71") (name "Net-(IC5-11_OUT6)") (class "Default")
      (node (ref "IC5") (pin "11") (pinfunction "11_OUT6_11") (pintype "output"))
      (node (ref "SW6") (pin "P-") (pinfunction "P_P-") (pintype "bidirectional"))
    )
    (net (code "72") (name "Net-(IC5-12_OUT7)") (class "Default")
      (node (ref "IC5") (pin "12") (pinfunction "12_OUT7_12") (pintype "output"))
      (node (ref "SW6") (pin "G2") (pinfunction "G2_G2") (pintype "bidirectional"))
    )
    (net (code "73") (name "Net-(IC5-14_SDO)") (class "Default")
      (node (ref "IC5") (pin "14") (pinfunction "14_SDO_14") (pintype "output"))
      (node (ref "IC6") (pin "2") (pinfunction "02_SDI_2") (pintype "input"))
      (node (ref "SJ3") (pin "2") (pinfunction "2_2") (pintype "passive"))
      (node (ref "SJ4") (pin "3") (pinfunction "1_3") (pintype "passive"))
    )
    (net (code "74") (name "Net-(IC5-15_REXT)") (class "Default")
      (node (ref "IC5") (pin "15") (pinfunction "15_REXT_15") (pintype "bidirectional"))
      (node (ref "R21") (pin "1") (pinfunction "A_1") (pintype "passive"))
    )
    (net (code "75") (name "Net-(IC6-06_OUT1)") (class "Default")
      (node (ref "IC6") (pin "6") (pinfunction "06_OUT1_6") (pintype "output"))
      (node (ref "SW7") (pin "Z-") (pinfunction "Z_Z-") (pintype "bidirectional"))
    )
    (net (code "76") (name "Net-(IC6-07_OUT2)") (class "Default")
      (node (ref "IC6") (pin "7") (pinfunction "07_OUT2_7") (pintype "output"))
      (node (ref "SW7") (pin "P-") (pinfunction "P_P-") (pintype "bidirectional"))
    )
    (net (code "77") (name "Net-(IC6-08_OUT3)") (class "Default")
      (node (ref "IC6") (pin "8") (pinfunction "08_OUT3_8") (pintype "output"))
      (node (ref "SW7") (pin "G2") (pinfunction "G2_G2") (pintype "bidirectional"))
    )
    (net (code "78") (name "Net-(IC6-10_OUT5)") (class "Default")
      (node (ref "IC6") (pin "10") (pinfunction "10_OUT5_10") (pintype "output"))
      (node (ref "SW8") (pin "Z-") (pinfunction "Z_Z-") (pintype "bidirectional"))
    )
    (net (code "79") (name "Net-(IC6-11_OUT6)") (class "Default")
      (node (ref "IC6") (pin "11") (pinfunction "11_OUT6_11") (pintype "output"))
      (node (ref "SW8") (pin "P-") (pinfunction "P_P-") (pintype "bidirectional"))
    )
    (net (code "80") (name "Net-(IC6-12_OUT7)") (class "Default")
      (node (ref "IC6") (pin "12") (pinfunction "12_OUT7_12") (pintype "output"))
      (node (ref "SW8") (pin "G2") (pinfunction "G2_G2") (pintype "bidirectional"))
    )
    (net (code "81") (name "Net-(IC6-14_SDO)") (class "Default")
      (node (ref "IC6") (pin "14") (pinfunction "14_SDO_14") (pintype "output"))
      (node (ref "IC7") (pin "2") (pinfunction "02_SDI_2") (pintype "input"))
      (node (ref "SJ4") (pin "2") (pinfunction "2_2") (pintype "passive"))
      (node (ref "SJ5") (pin "3") (pinfunction "1_3") (pintype "passive"))
    )
    (net (code "82") (name "Net-(IC6-15_REXT)") (class "Default")
      (node (ref "IC6") (pin "15") (pinfunction "15_REXT_15") (pintype "bidirectional"))
      (node (ref "R22") (pin "1") (pinfunction "A_1") (pintype "passive"))
    )
    (net (code "83") (name "Net-(IC7-06_OUT1)") (class "Default")
      (node (ref "IC7") (pin "6") (pinfunction "06_OUT1_6") (pintype "output"))
      (node (ref "SW9") (pin "Z-") (pinfunction "Z_Z-") (pintype "bidirectional"))
    )
    (net (code "84") (name "Net-(IC7-07_OUT2)") (class "Default")
      (node (ref "IC7") (pin "7") (pinfunction "07_OUT2_7") (pintype "output"))
      (node (ref "SW9") (pin "P-") (pinfunction "P_P-") (pintype "bidirectional"))
    )
    (net (code "85") (name "Net-(IC7-08_OUT3)") (class "Default")
      (node (ref "IC7") (pin "8") (pinfunction "08_OUT3_8") (pintype "output"))
      (node (ref "SW9") (pin "G2") (pinfunction "G2_G2") (pintype "bidirectional"))
    )
    (net (code "86") (name "Net-(IC7-10_OUT5)") (class "Default")
      (node (ref "IC7") (pin "10") (pinfunction "10_OUT5_10") (pintype "output"))
      (node (ref "SW10") (pin "Z-") (pinfunction "Z_Z-") (pintype "bidirectional"))
    )
    (net (code "87") (name "Net-(IC7-11_OUT6)") (class "Default")
      (node (ref "IC7") (pin "11") (pinfunction "11_OUT6_11") (pintype "output"))
      (node (ref "SW10") (pin "P-") (pinfunction "P_P-") (pintype "bidirectional"))
    )
    (net (code "88") (name "Net-(IC7-12_OUT7)") (class "Default")
      (node (ref "IC7") (pin "12") (pinfunction "12_OUT7_12") (pintype "output"))
      (node (ref "SW10") (pin "G2") (pinfunction "G2_G2") (pintype "bidirectional"))
    )
    (net (code "89") (name "Net-(IC7-15_REXT)") (class "Default")
      (node (ref "IC7") (pin "15") (pinfunction "15_REXT_15") (pintype "bidirectional"))
      (node (ref "R13") (pin "1") (pinfunction "A_1") (pintype "passive"))
    )
    (net (code "90") (name "Net-(PIC1-01_~{MCLR})") (class "Default")
      (node (ref "PIC1") (pin "1") (pinfunction "01_~{MCLR}_1") (pintype "input"))
      (node (ref "PROG") (pin "3") (pinfunction "3_3") (pintype "passive"))
      (node (ref "R9") (pin "1") (pinfunction "A_1") (pintype "passive"))
    )
    (net (code "91") (name "Net-(PIC1-06_AN4{slash}C1INB{slash}C2IND{slash}RPB2{slash}SDA2{slash}CTED13{slash}RB2)") (class "Default")
      (node (ref "PIC1") (pin "6") (pinfunction "06_AN4/C1INB/C2IND/RPB2/SDA2/CTED13/RB2_6") (pintype "bidirectional"))
      (node (ref "R17") (pin "1") (pinfunction "A_1") (pintype "passive"))
      (node (ref "R79") (pin "1") (pinfunction "A_1") (pintype "passive"))
    )
    (net (code "92") (name "Net-(PIC1-09_OSC1{slash}CLKI{slash}RPA2{slash}RA2)") (class "Default")
      (node (ref "C1") (pin "1") (pinfunction "1_1") (pintype "passive"))
      (node (ref "PIC1") (pin "9") (pinfunction "09_OSC1/CLKI/RPA2/RA2_9") (pintype "bidirectional"))
      (node (ref "Q1") (pin "P$2") (pinfunction "2_P$2") (pintype "passive"))
    )
    (net (code "93") (name "Net-(PIC1-10_OSC2{slash}CLKO{slash}RPA3{slash}PMA0{slash}RA3)") (class "Default")
      (node (ref "C2") (pin "1") (pinfunction "1_1") (pintype "passive"))
      (node (ref "PIC1") (pin "10") (pinfunction "10_OSC2/CLKO/RPA3/PMA0/RA3_10") (pintype "bidirectional"))
      (node (ref "Q1") (pin "P$1") (pinfunction "1_P$1") (pintype "passive"))
    )
    (net (code "94") (name "Net-(PIC1-12_SOSCO{slash}RPA4{slash}T1CK{slash}CTED9{slash}PMA1{slash}RA4)") (class "Default")
      (node (ref "PIC1") (pin "12") (pinfunction "12_SOSCO/RPA4/T1CK/CTED9/PMA1/RA4_12") (pintype "bidirectional"))
      (node (ref "R28") (pin "2") (pinfunction "E_2") (pintype "passive"))
      (node (ref "R31") (pin "1") (pinfunction "A_1") (pintype "passive"))
    )
    (net (code "95") (name "Net-(PIC1-14_PGED3{slash}RPB5{slash}PMD7{slash}RB5)") (class "Default")
      (node (ref "CN_SYSTEM") (pin "11") (pinfunction "11_11") (pintype "passive"))
      (node (ref "CN_SYSTEM") (pin "12") (pinfunction "12_12") (pintype "passive"))
      (node (ref "PIC1") (pin "14") (pinfunction "14_PGED3/RPB5/PMD7/RB5_14") (pintype "bidirectional"))
      (node (ref "PROG") (pin "4") (pinfunction "4_4") (pintype "passive"))
    )
    (net (code "96") (name "Net-(PIC1-15_PGEC3{slash}RPB6{slash}PMD6{slash}RB6)") (class "Default")
      (node (ref "PIC1") (pin "15") (pinfunction "15_PGEC3/RPB6/PMD6/RB6_15") (pintype "bidirectional"))
      (node (ref "PROG") (pin "5") (pinfunction "5_5") (pintype "passive"))
      (node (ref "R27") (pin "2") (pinfunction "E_2") (pintype "passive"))
      (node (ref "SW1") (pin "G1") (pinfunction "G1_G1") (pintype "bidirectional"))
      (node (ref "SW10") (pin "G1") (pinfunction "G1_G1") (pintype "bidirectional"))
      (node (ref "SW2") (pin "G1") (pinfunction "G1_G1") (pintype "bidirectional"))
      (node (ref "SW3") (pin "G1") (pinfunction "G1_G1") (pintype "bidirectional"))
      (node (ref "SW4") (pin "G1") (pinfunction "G1_G1") (pintype "bidirectional"))
      (node (ref "SW5") (pin "G1") (pinfunction "G1_G1") (pintype "bidirectional"))
      (node (ref "SW6") (pin "G1") (pinfunction "G1_G1") (pintype "bidirectional"))
      (node (ref "SW7") (pin "G1") (pinfunction "G1_G1") (pintype "bidirectional"))
      (node (ref "SW8") (pin "G1") (pinfunction "G1_G1") (pintype "bidirectional"))
      (node (ref "SW9") (pin "G1") (pinfunction "G1_G1") (pintype "bidirectional"))
    )
    (net (code "97") (name "Net-(PIC1-16_TDI{slash}RPB7{slash}CTED3{slash}PMD5{slash}INT0{slash}RB7)") (class "Default")
      (node (ref "CN_SYSTEM") (pin "13") (pinfunction "13_13") (pintype "passive"))
      (node (ref "CN_SYSTEM") (pin "14") (pinfunction "14_14") (pintype "passive"))
      (node (ref "PIC1") (pin "16") (pinfunction "16_TDI/RPB7/CTED3/PMD5/INT0/RB7_16") (pintype "bidirectional"))
    )
    (net (code "98") (name "Net-(PIC1-17_TCK{slash}RPB8{slash}SCL1{slash}CTED10{slash}PMD4{slash}RB8)") (class "Default")
      (node (ref "PIC1") (pin "17") (pinfunction "17_TCK/RPB8/SCL1/CTED10/PMD4/RB8_17") (pintype "bidirectional"))
      (node (ref "R29") (pin "1") (pinfunction "A_1") (pintype "passive"))
    )
    (net (code "99") (name "Net-(PIC1-18_TDO{slash}RPB9{slash}SDA1{slash}CTED4{slash}PMD3{slash}RB9)") (class "Default")
      (node (ref "PIC1") (pin "18") (pinfunction "18_TDO/RPB9/SDA1/CTED4/PMD3/RB9_18") (pintype "bidirectional"))
      (node (ref "R30") (pin "1") (pinfunction "A_1") (pintype "passive"))
    )
    (net (code "100") (name "Net-(PIC1-20_VCAP)") (class "Default")
      (node (ref "C6") (pin "1") (pinfunction "1_1") (pintype "passive"))
      (node (ref "PIC1") (pin "20") (pinfunction "20_VCAP_20") (pintype "power_in"))
    )
    (net (code "101") (name "Net-(PIC1-24_AN11{slash}RPB13{slash}CTPLS{slash}PMRD{slash}RB13)") (class "Default")
      (node (ref "CN_SYSTEM") (pin "10") (pinfunction "10_10") (pintype "passive"))
      (node (ref "CN_SYSTEM") (pin "9") (pinfunction "9_9") (pintype "passive"))
      (node (ref "PIC1") (pin "24") (pinfunction "24_AN11/RPB13/CTPLS/PMRD/RB13_24") (pintype "bidirectional"))
    )
    (net (code "102") (name "Net-(PIC1-25_CVREFOUT{slash}AN10{slash}C3INB{slash}RPB14{slash}SCK1{slash}CTED5{slash}PMWR{slash}RB14)") (class "Default")
      (node (ref "CN_SYSTEM") (pin "7") (pinfunction "7_7") (pintype "passive"))
      (node (ref "CN_SYSTEM") (pin "8") (pinfunction "8_8") (pintype "passive"))
      (node (ref "PIC1") (pin "25") (pinfunction "25_CVREFOUT/AN10/C3INB/RPB14/SCK1/CTED5/PMWR/RB14_25") (pintype "bidirectional"))
      (node (ref "R14") (pin "1") (pinfunction "A_1") (pintype "passive"))
    )
    (net (code "103") (name "Net-(Q2-B)") (class "Default")
      (node (ref "Q2") (pin "1") (pinfunction "B_1") (pintype "passive"))
      (node (ref "R17") (pin "2") (pinfunction "E_2") (pintype "passive"))
    )
    (net (code "104") (name "Net-(Q2-C)") (class "Default")
      (node (ref "Q2") (pin "3") (pinfunction "C_3") (pintype "passive"))
      (node (ref "R26") (pin "2") (pinfunction "E_2") (pintype "passive"))
    )
    (net (code "105") (name "Net-(R1-E)") (class "Default")
      (node (ref "R1") (pin "2") (pinfunction "E_2") (pintype "passive"))
      (node (ref "R11") (pin "2") (pinfunction "E_2") (pintype "passive"))
      (node (ref "R12") (pin "1") (pinfunction "A_1") (pintype "passive"))
      (node (ref "R2") (pin "1") (pinfunction "A_1") (pintype "passive"))
      (node (ref "R26") (pin "1") (pinfunction "A_1") (pintype "passive"))
      (node (ref "R3") (pin "2") (pinfunction "E_2") (pintype "passive"))
      (node (ref "R4") (pin "1") (pinfunction "A_1") (pintype "passive"))
      (node (ref "R5") (pin "2") (pinfunction "E_2") (pintype "passive"))
      (node (ref "R6") (pin "1") (pinfunction "A_1") (pintype "passive"))
      (node (ref "R7") (pin "2") (pinfunction "E_2") (pintype "passive"))
      (node (ref "R8") (pin "1") (pinfunction "A_1") (pintype "passive"))
    )
    (net (code "106") (name "Net-(R10-E)") (class "Default")
      (node (ref "C20") (pin "P+") (pinfunction "P+_P+") (pintype "passive"))
      (node (ref "R10") (pin "2") (pinfunction "E_2") (pintype "passive"))
      (node (ref "R13") (pin "2") (pinfunction "E_2") (pintype "passive"))
      (node (ref "R18") (pin "2") (pinfunction "E_2") (pintype "passive"))
      (node (ref "R19") (pin "2") (pinfunction "E_2") (pintype "passive"))
      (node (ref "R20") (pin "2") (pinfunction "E_2") (pintype "passive"))
      (node (ref "R21") (pin "2") (pinfunction "E_2") (pintype "passive"))
      (node (ref "R22") (pin "2") (pinfunction "E_2") (pintype "passive"))
      (node (ref "R31") (pin "2") (pinfunction "E_2") (pintype "passive"))
      (node (ref "R32") (pin "1") (pinfunction "A_1") (pintype "passive"))
    )
    (net (code "107") (name "Net-(R51-A)") (class "Default")
      (node (ref "C28") (pin "2") (pinfunction "2_2") (pintype "passive"))
      (node (ref "R51") (pin "1") (pinfunction "A_1") (pintype "passive"))
    )
    (net (code "108") (name "unconnected-(IC1-11_OUT6-Pad11)") (class "Default")
      (node (ref "IC1") (pin "11") (pinfunction "11_OUT6_11") (pintype "output"))
    )
    (net (code "109") (name "unconnected-(IC1-12_OUT7-Pad12)") (class "Default")
      (node (ref "IC1") (pin "12") (pinfunction "12_OUT7_12") (pintype "output"))
    )
    (net (code "110") (name "unconnected-(IC2-11_OUT6-Pad11)") (class "Default")
      (node (ref "IC2") (pin "11") (pinfunction "11_OUT6_11") (pintype "output"))
    )
    (net (code "111") (name "unconnected-(IC2-12_OUT7-Pad12)") (class "Default")
      (node (ref "IC2") (pin "12") (pinfunction "12_OUT7_12") (pintype "output"))
    )
    (net (code "112") (name "unconnected-(PIC1-02_VREF+{slash}VREF+{slash}AN0{slash}C3INC{slash}RPA0{slash}CTED1{slash}RA0-Pad2)") (class "Default")
      (node (ref "PIC1") (pin "2") (pinfunction "02_VREF+/VREF+/AN0/C3INC/RPA0/CTED1/RA0_2") (pintype "bidirectional"))
    )
    (net (code "113") (name "unconnected-(PIC1-03_VREF-{slash}CVREF-{slash}AN1{slash}RPA1{slash}CTED2{slash}RA1-Pad3)") (class "Default")
      (node (ref "PIC1") (pin "3") (pinfunction "03_VREF-/CVREF-/AN1/RPA1/CTED2/RA1_3") (pintype "bidirectional"))
    )
    (net (code "114") (name "unconnected-(PIC1-04_PGED1{slash}AN2{slash}C1IND{slash}C2INB{slash}C3IND{slash}RPB0{slash}RB0-Pad4)") (class "Default")
      (node (ref "PIC1") (pin "4") (pinfunction "04_PGED1/AN2/C1IND/C2INB/C3IND/RPB0/RB0_4") (pintype "bidirectional"))
    )
    (net (code "115") (name "unconnected-(PIC1-05_PGEC1{slash}AN3{slash}C1INC{slash}C2INA{slash}RPB1{slash}CTED12{slash}RB1-Pad5)") (class "Default")
      (node (ref "PIC1") (pin "5") (pinfunction "05_PGEC1/AN3/C1INC/C2INA/RPB1/CTED12/RB1_5") (pintype "bidirectional"))
    )
    (net (code "116") (name "unconnected-(PIC1-07_AN5{slash}C1INA{slash}C2INC{slash}RTCC{slash}RPB3{slash}SCL2{slash}RB3-Pad7)") (class "Default")
      (node (ref "PIC1") (pin "7") (pinfunction "07_AN5/C1INA/C2INC/RTCC/RPB3/SCL2/RB3_7") (pintype "bidirectional"))
    )
    (net (code "117") (name "unconnected-(PIC1-11_SOSCI{slash}RPB4{slash}RB4-Pad11)") (class "Default")
      (node (ref "PIC1") (pin "11") (pinfunction "11_SOSCI/RPB4/RB4_11") (pintype "bidirectional"))
    )
  )
)
